# ArduFrauenfelderCNC_0_1-b8.net
KiCad netlist of a schematic drawn in EAGLE
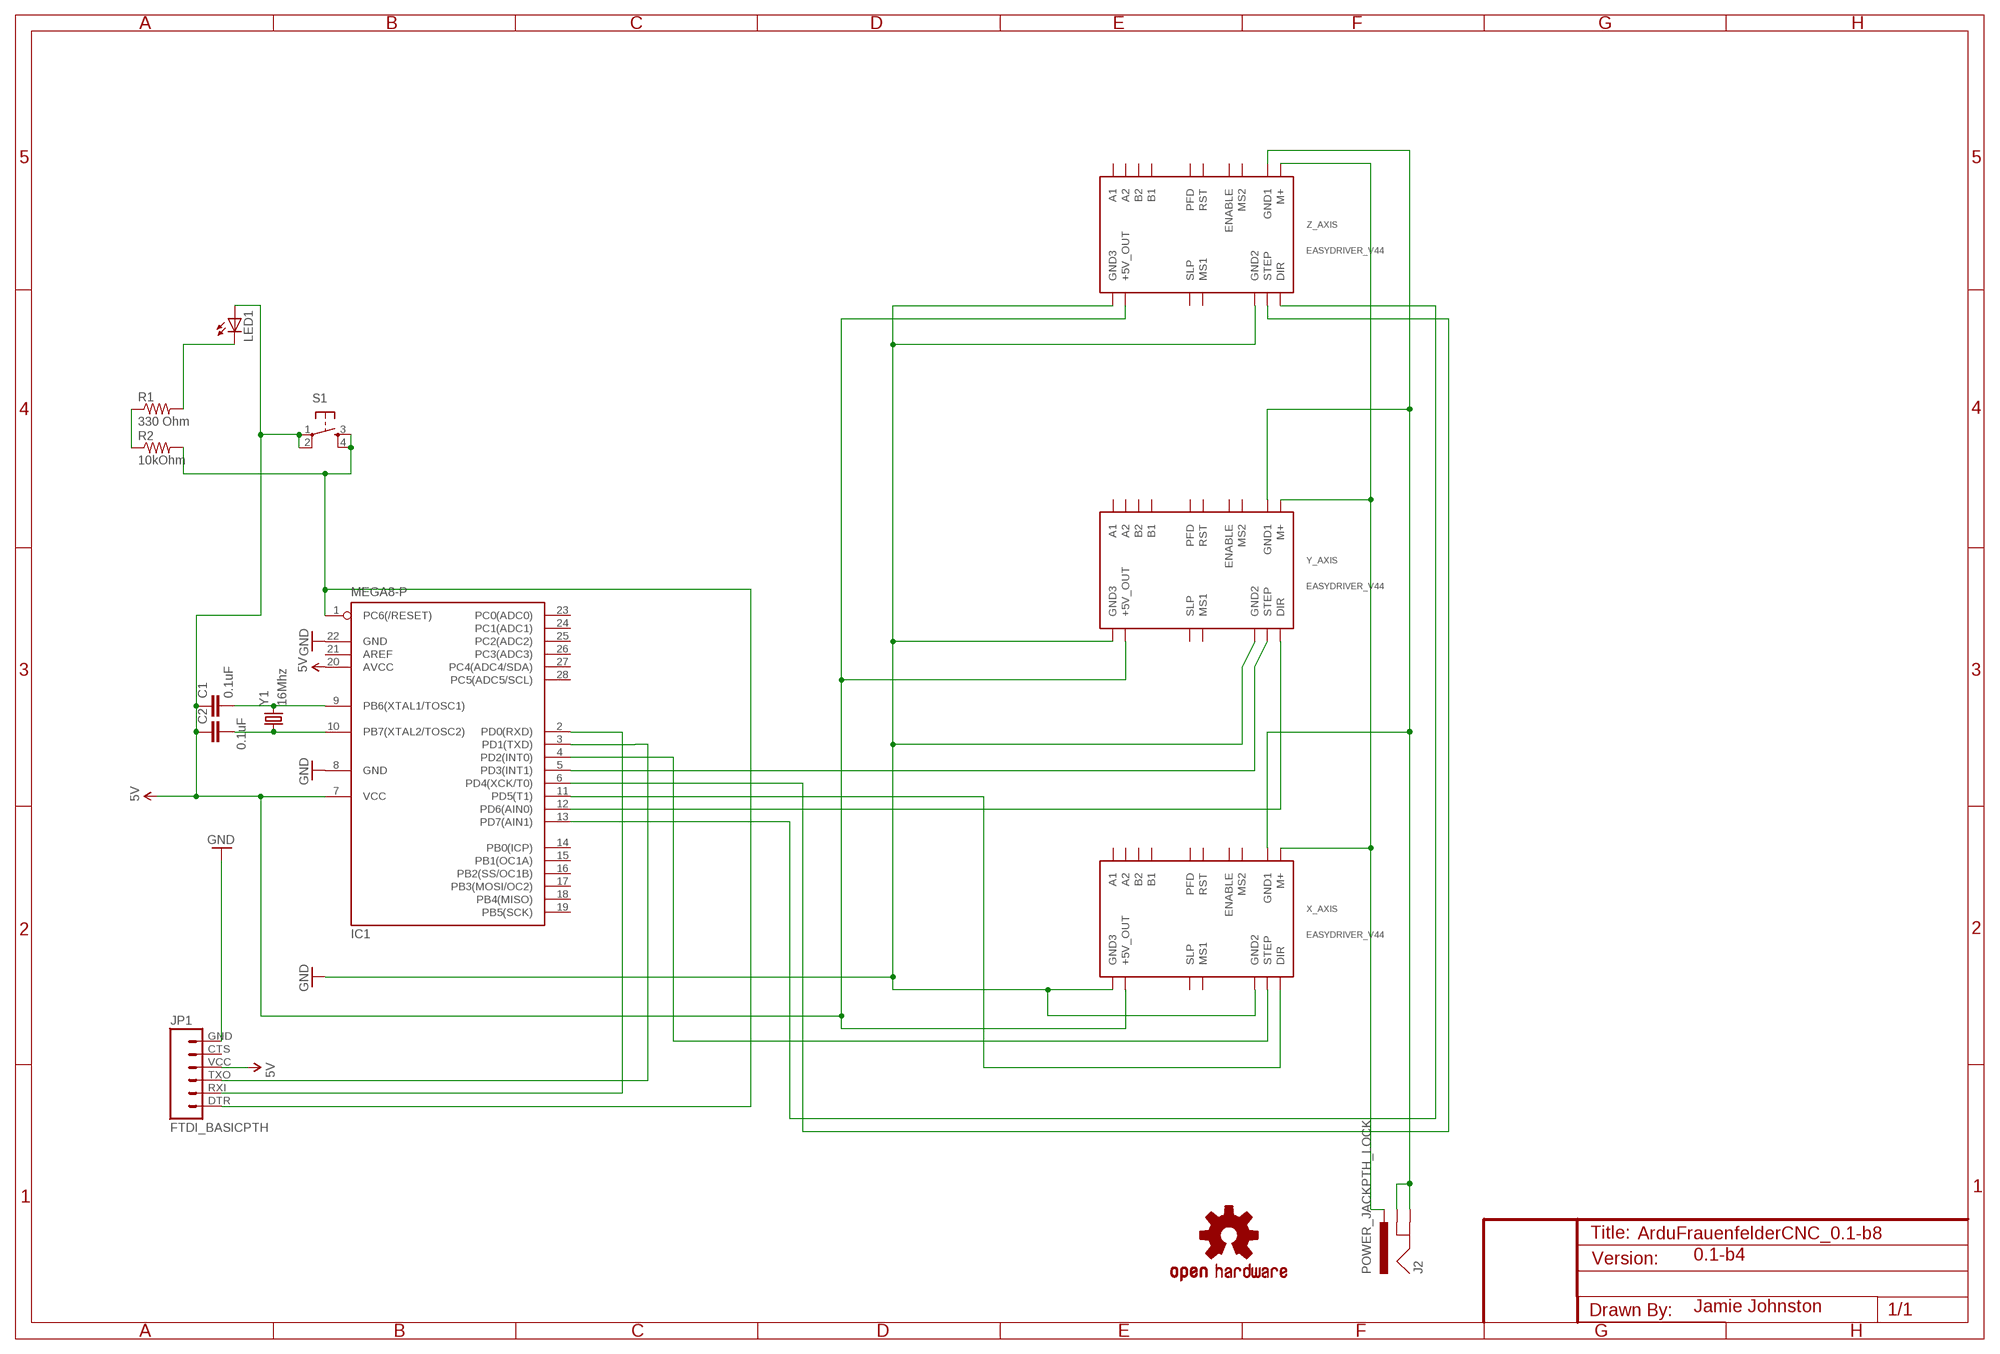
[diagram p0: schematic, sheet 1]

(export (version "E")
  (design (tool "Eeschema 10.0.6"))
  (components
    (comp (ref "C1")
      (value "0.1uF")
      (footprint "eagle-import:CAP-PTH-SMALL")
      (libsource (lib "eagle-import") (part "CAPPTH"))
    )
    (comp (ref "C2")
      (value "0.1uF")
      (footprint "eagle-import:CAP-PTH-SMALL")
      (libsource (lib "eagle-import") (part "CAPPTH"))
    )
    (comp (ref "IC1")
      (value "MEGA8-P")
      (footprint "eagle-import:DIL28-3")
      (libsource (lib "eagle-import") (part "MEGA8-P"))
    )
    (comp (ref "J2")
      (value "POWER_JACKPTH_LOCK")
      (footprint "eagle-import:POWER_JACK_PTH_LOCK")
      (libsource (lib "eagle-import") (part "POWER_JACKPTH_LOCK"))
    )
    (comp (ref "JP1")
      (value "FTDI_BASICPTH")
      (footprint "eagle-import:FTDI_BASIC")
      (libsource (lib "eagle-import") (part "FTDI_BASICPTH"))
    )
    (comp (ref "LED1")
      (value "LED5MM")
      (footprint "eagle-import:LED5MM")
      (libsource (lib "eagle-import") (part "LED5MM"))
    )
    (comp (ref "R1")
      (value "330 Ohm")
      (footprint "eagle-import:AXIAL-0.4")
      (libsource (lib "eagle-import") (part "RESISTORPTH-1/4W"))
    )
    (comp (ref "R2")
      (value "10kOhm")
      (footprint "eagle-import:AXIAL-0.4")
      (libsource (lib "eagle-import") (part "RESISTORPTH-1/4W"))
    )
    (comp (ref "S1")
      (value "TAC_SWITCHPTH")
      (footprint "eagle-import:TACTILE-PTH")
      (libsource (lib "eagle-import") (part "TAC_SWITCHPTH"))
    )
    (comp (ref "U$2")
      (value "OSHW-LOGOL")
      (footprint "eagle-import:OSHW-LOGO-L")
      (libsource (lib "eagle-import") (part "OSHW-LOGOL"))
    )
    (comp (ref "X_AXIS")
      (value "EASYDRIVER_V44")
      (footprint "eagle-import:EASYDRIVER_V44")
      (libsource (lib "eagle-import") (part "EASYDRIVER_V44"))
    )
    (comp (ref "Y1")
      (value "16Mhz")
      (footprint "eagle-import:HC49US")
      (libsource (lib "eagle-import") (part "CRYSTALHC49US"))
    )
    (comp (ref "Y_AXIS")
      (value "EASYDRIVER_V44")
      (footprint "eagle-import:EASYDRIVER_V44")
      (libsource (lib "eagle-import") (part "EASYDRIVER_V44"))
    )
    (comp (ref "Z_AXIS")
      (value "EASYDRIVER_V44")
      (footprint "eagle-import:EASYDRIVER_V44")
      (libsource (lib "eagle-import") (part "EASYDRIVER_V44"))
    )
  )
  (nets
    (net (code "1") (name "5V") (class "Default")
      (node (ref "C1") (pin "1") (pinfunction "1_1") (pintype "passive"))
      (node (ref "C2") (pin "1") (pinfunction "1_1") (pintype "passive"))
      (node (ref "IC1") (pin "20") (pinfunction "AVCC_20") (pintype "power_in"))
      (node (ref "IC1") (pin "7") (pinfunction "VCC_7") (pintype "power_in"))
      (node (ref "JP1") (pin "VCC") (pinfunction "4_VCC") (pintype "passive"))
      (node (ref "LED1") (pin "A") (pinfunction "A_A") (pintype "passive"))
      (node (ref "S1") (pin "1") (pinfunction "1_1") (pintype "passive"))
      (node (ref "S1") (pin "2") (pinfunction "2_2") (pintype "passive"))
      (node (ref "X_AXIS") (pin "P$11") (pinfunction "+5V_OUT_P$11") (pintype "bidirectional"))
      (node (ref "Y_AXIS") (pin "P$11") (pinfunction "+5V_OUT_P$11") (pintype "bidirectional"))
      (node (ref "Z_AXIS") (pin "P$11") (pinfunction "+5V_OUT_P$11") (pintype "bidirectional"))
    )
    (net (code "2") (name "GND") (class "Default")
      (node (ref "IC1") (pin "22") (pinfunction "GND_22") (pintype "power_in"))
      (node (ref "IC1") (pin "8") (pinfunction "GND_8") (pintype "power_in"))
      (node (ref "JP1") (pin "GND") (pinfunction "6_GND") (pintype "passive"))
      (node (ref "X_AXIS") (pin "GND2") (pinfunction "GND2_GND2") (pintype "bidirectional"))
      (node (ref "X_AXIS") (pin "GND3") (pinfunction "GND3_GND3") (pintype "bidirectional"))
      (node (ref "Y_AXIS") (pin "GND2") (pinfunction "GND2_GND2") (pintype "bidirectional"))
      (node (ref "Y_AXIS") (pin "GND3") (pinfunction "GND3_GND3") (pintype "bidirectional"))
      (node (ref "Z_AXIS") (pin "GND2") (pinfunction "GND2_GND2") (pintype "bidirectional"))
      (node (ref "Z_AXIS") (pin "GND3") (pinfunction "GND3_GND3") (pintype "bidirectional"))
    )
    (net (code "3") (name "Net-(IC1-PB6(XTAL1{slash}TOSC1))") (class "Default")
      (node (ref "C1") (pin "2") (pinfunction "2_2") (pintype "passive"))
      (node (ref "IC1") (pin "9") (pinfunction "PB6(XTAL1/TOSC1)_9") (pintype "bidirectional"))
      (node (ref "Y1") (pin "2") (pinfunction "2_2") (pintype "passive"))
    )
    (net (code "4") (name "Net-(IC1-PB7(XTAL2{slash}TOSC2))") (class "Default")
      (node (ref "C2") (pin "2") (pinfunction "2_2") (pintype "passive"))
      (node (ref "IC1") (pin "10") (pinfunction "PB7(XTAL2/TOSC2)_10") (pintype "bidirectional"))
      (node (ref "Y1") (pin "1") (pinfunction "1_1") (pintype "passive"))
    )
    (net (code "5") (name "Net-(IC1-PC6({slash}RESET))") (class "Default")
      (node (ref "IC1") (pin "1") (pinfunction "PC6(/RESET)_1") (pintype "bidirectional"))
      (node (ref "JP1") (pin "DTR") (pinfunction "1_DTR") (pintype "passive"))
      (node (ref "R2") (pin "P$2") (pinfunction "2_P$2") (pintype "passive"))
      (node (ref "S1") (pin "3") (pinfunction "3_3") (pintype "passive"))
      (node (ref "S1") (pin "4") (pinfunction "4_4") (pintype "passive"))
    )
    (net (code "6") (name "Net-(IC1-PD0(RXD))") (class "Default")
      (node (ref "IC1") (pin "2") (pinfunction "PD0(RXD)_2") (pintype "bidirectional"))
      (node (ref "JP1") (pin "RXI") (pinfunction "2_RXI") (pintype "passive"))
    )
    (net (code "7") (name "Net-(IC1-PD1(TXD))") (class "Default")
      (node (ref "IC1") (pin "3") (pinfunction "PD1(TXD)_3") (pintype "bidirectional"))
      (node (ref "JP1") (pin "TXO") (pinfunction "3_TXO") (pintype "passive"))
    )
    (net (code "8") (name "Net-(IC1-PD2(INT0))") (class "Default")
      (node (ref "IC1") (pin "4") (pinfunction "PD2(INT0)_4") (pintype "bidirectional"))
      (node (ref "X_AXIS") (pin "STEP") (pinfunction "STEP_STEP") (pintype "bidirectional"))
    )
    (net (code "9") (name "Net-(IC1-PD3(INT1))") (class "Default")
      (node (ref "IC1") (pin "5") (pinfunction "PD3(INT1)_5") (pintype "bidirectional"))
      (node (ref "Y_AXIS") (pin "STEP") (pinfunction "STEP_STEP") (pintype "bidirectional"))
    )
    (net (code "10") (name "Net-(IC1-PD4(XCK{slash}T0))") (class "Default")
      (node (ref "IC1") (pin "6") (pinfunction "PD4(XCK/T0)_6") (pintype "bidirectional"))
      (node (ref "Z_AXIS") (pin "STEP") (pinfunction "STEP_STEP") (pintype "bidirectional"))
    )
    (net (code "11") (name "Net-(IC1-PD5(T1))") (class "Default")
      (node (ref "IC1") (pin "11") (pinfunction "PD5(T1)_11") (pintype "bidirectional"))
      (node (ref "X_AXIS") (pin "DIR") (pinfunction "DIR_DIR") (pintype "bidirectional"))
    )
    (net (code "12") (name "Net-(IC1-PD6(AIN0))") (class "Default")
      (node (ref "IC1") (pin "12") (pinfunction "PD6(AIN0)_12") (pintype "bidirectional"))
      (node (ref "Y_AXIS") (pin "DIR") (pinfunction "DIR_DIR") (pintype "bidirectional"))
    )
    (net (code "13") (name "Net-(IC1-PD7(AIN1))") (class "Default")
      (node (ref "IC1") (pin "13") (pinfunction "PD7(AIN1)_13") (pintype "bidirectional"))
      (node (ref "Z_AXIS") (pin "DIR") (pinfunction "DIR_DIR") (pintype "bidirectional"))
    )
    (net (code "14") (name "Net-(J2-PadGND)") (class "Default")
      (node (ref "J2") (pin "GND") (pinfunction "GND_GND") (pintype "bidirectional"))
      (node (ref "J2") (pin "GNDBREAK") (pinfunction "GNDBREAK_GNDBREAK") (pintype "bidirectional"))
      (node (ref "X_AXIS") (pin "GND1") (pinfunction "GND1_GND1") (pintype "bidirectional"))
      (node (ref "Y_AXIS") (pin "GND1") (pinfunction "GND1_GND1") (pintype "bidirectional"))
      (node (ref "Z_AXIS") (pin "GND1") (pinfunction "GND1_GND1") (pintype "bidirectional"))
    )
    (net (code "15") (name "Net-(J2-PadPWR)") (class "Default")
      (node (ref "J2") (pin "PWR") (pinfunction "PWR_PWR") (pintype "bidirectional"))
      (node (ref "X_AXIS") (pin "M+") (pinfunction "M+_M+") (pintype "bidirectional"))
      (node (ref "Y_AXIS") (pin "M+") (pinfunction "M+_M+") (pintype "bidirectional"))
      (node (ref "Z_AXIS") (pin "M+") (pinfunction "M+_M+") (pintype "bidirectional"))
    )
    (net (code "16") (name "Net-(LED1-C)") (class "Default")
      (node (ref "LED1") (pin "K") (pinfunction "C_K") (pintype "passive"))
      (node (ref "R1") (pin "P$2") (pinfunction "2_P$2") (pintype "passive"))
    )
    (net (code "17") (name "Net-(R1-1)") (class "Default")
      (node (ref "R1") (pin "P$1") (pinfunction "1_P$1") (pintype "passive"))
      (node (ref "R2") (pin "P$1") (pinfunction "1_P$1") (pintype "passive"))
    )
    (net (code "18") (name "unconnected-(IC1-AREF-Pad21)") (class "Default")
      (node (ref "IC1") (pin "21") (pinfunction "AREF_21") (pintype "passive"))
    )
    (net (code "19") (name "unconnected-(IC1-PB0(ICP)-Pad14)") (class "Default")
      (node (ref "IC1") (pin "14") (pinfunction "PB0(ICP)_14") (pintype "bidirectional"))
    )
    (net (code "20") (name "unconnected-(IC1-PB1(OC1A)-Pad15)") (class "Default")
      (node (ref "IC1") (pin "15") (pinfunction "PB1(OC1A)_15") (pintype "bidirectional"))
    )
    (net (code "21") (name "unconnected-(IC1-PB2(SS{slash}OC1B)-Pad16)") (class "Default")
      (node (ref "IC1") (pin "16") (pinfunction "PB2(SS/OC1B)_16") (pintype "bidirectional"))
    )
    (net (code "22") (name "unconnected-(IC1-PB3(MOSI{slash}OC2)-Pad17)") (class "Default")
      (node (ref "IC1") (pin "17") (pinfunction "PB3(MOSI/OC2)_17") (pintype "bidirectional"))
    )
    (net (code "23") (name "unconnected-(IC1-PB4(MISO)-Pad18)") (class "Default")
      (node (ref "IC1") (pin "18") (pinfunction "PB4(MISO)_18") (pintype "bidirectional"))
    )
    (net (code "24") (name "unconnected-(IC1-PB5(SCK)-Pad19)") (class "Default")
      (node (ref "IC1") (pin "19") (pinfunction "PB5(SCK)_19") (pintype "bidirectional"))
    )
    (net (code "25") (name "unconnected-(IC1-PC0(ADC0)-Pad23)") (class "Default")
      (node (ref "IC1") (pin "23") (pinfunction "PC0(ADC0)_23") (pintype "bidirectional"))
    )
    (net (code "26") (name "unconnected-(IC1-PC1(ADC1)-Pad24)") (class "Default")
      (node (ref "IC1") (pin "24") (pinfunction "PC1(ADC1)_24") (pintype "bidirectional"))
    )
    (net (code "27") (name "unconnected-(IC1-PC2(ADC2)-Pad25)") (class "Default")
      (node (ref "IC1") (pin "25") (pinfunction "PC2(ADC2)_25") (pintype "bidirectional"))
    )
    (net (code "28") (name "unconnected-(IC1-PC3(ADC3)-Pad26)") (class "Default")
      (node (ref "IC1") (pin "26") (pinfunction "PC3(ADC3)_26") (pintype "bidirectional"))
    )
    (net (code "29") (name "unconnected-(IC1-PC4(ADC4{slash}SDA)-Pad27)") (class "Default")
      (node (ref "IC1") (pin "27") (pinfunction "PC4(ADC4/SDA)_27") (pintype "bidirectional"))
    )
    (net (code "30") (name "unconnected-(IC1-PC5(ADC5{slash}SCL)-Pad28)") (class "Default")
      (node (ref "IC1") (pin "28") (pinfunction "PC5(ADC5/SCL)_28") (pintype "bidirectional"))
    )
    (net (code "31") (name "unconnected-(JP1-5-PadCTS)") (class "Default")
      (node (ref "JP1") (pin "CTS") (pinfunction "5_CTS") (pintype "passive"))
    )
    (net (code "32") (name "unconnected-(X_AXIS-PadA1)") (class "Default")
      (node (ref "X_AXIS") (pin "A1") (pinfunction "A1_A1") (pintype "bidirectional"))
    )
    (net (code "33") (name "unconnected-(X_AXIS-PadA2)") (class "Default")
      (node (ref "X_AXIS") (pin "A2") (pinfunction "A2_A2") (pintype "bidirectional"))
    )
    (net (code "34") (name "unconnected-(X_AXIS-PadB1)") (class "Default")
      (node (ref "X_AXIS") (pin "B1") (pinfunction "B1_B1") (pintype "bidirectional"))
    )
    (net (code "35") (name "unconnected-(X_AXIS-PadB2)") (class "Default")
      (node (ref "X_AXIS") (pin "B2") (pinfunction "B2_B2") (pintype "bidirectional"))
    )
    (net (code "36") (name "unconnected-(X_AXIS-PadENABLE)") (class "Default")
      (node (ref "X_AXIS") (pin "ENABLE") (pinfunction "ENABLE_ENABLE") (pintype "bidirectional"))
    )
    (net (code "37") (name "unconnected-(X_AXIS-PadMS1)") (class "Default")
      (node (ref "X_AXIS") (pin "MS1") (pinfunction "MS1_MS1") (pintype "bidirectional"))
    )
    (net (code "38") (name "unconnected-(X_AXIS-PadMS2)") (class "Default")
      (node (ref "X_AXIS") (pin "MS2") (pinfunction "MS2_MS2") (pintype "bidirectional"))
    )
    (net (code "39") (name "unconnected-(X_AXIS-PadPFD)") (class "Default")
      (node (ref "X_AXIS") (pin "PFD") (pinfunction "PFD_PFD") (pintype "bidirectional"))
    )
    (net (code "40") (name "unconnected-(X_AXIS-PadRST)") (class "Default")
      (node (ref "X_AXIS") (pin "RST") (pinfunction "RST_RST") (pintype "bidirectional"))
    )
    (net (code "41") (name "unconnected-(X_AXIS-SLP-PadSLEEP)") (class "Default")
      (node (ref "X_AXIS") (pin "SLEEP") (pinfunction "SLP_SLEEP") (pintype "bidirectional"))
    )
    (net (code "42") (name "unconnected-(Y_AXIS-PadA1)") (class "Default")
      (node (ref "Y_AXIS") (pin "A1") (pinfunction "A1_A1") (pintype "bidirectional"))
    )
    (net (code "43") (name "unconnected-(Y_AXIS-PadA2)") (class "Default")
      (node (ref "Y_AXIS") (pin "A2") (pinfunction "A2_A2") (pintype "bidirectional"))
    )
    (net (code "44") (name "unconnected-(Y_AXIS-PadB1)") (class "Default")
      (node (ref "Y_AXIS") (pin "B1") (pinfunction "B1_B1") (pintype "bidirectional"))
    )
    (net (code "45") (name "unconnected-(Y_AXIS-PadB2)") (class "Default")
      (node (ref "Y_AXIS") (pin "B2") (pinfunction "B2_B2") (pintype "bidirectional"))
    )
    (net (code "46") (name "unconnected-(Y_AXIS-PadENABLE)") (class "Default")
      (node (ref "Y_AXIS") (pin "ENABLE") (pinfunction "ENABLE_ENABLE") (pintype "bidirectional"))
    )
    (net (code "47") (name "unconnected-(Y_AXIS-PadMS1)") (class "Default")
      (node (ref "Y_AXIS") (pin "MS1") (pinfunction "MS1_MS1") (pintype "bidirectional"))
    )
    (net (code "48") (name "unconnected-(Y_AXIS-PadMS2)") (class "Default")
      (node (ref "Y_AXIS") (pin "MS2") (pinfunction "MS2_MS2") (pintype "bidirectional"))
    )
    (net (code "49") (name "unconnected-(Y_AXIS-PadPFD)") (class "Default")
      (node (ref "Y_AXIS") (pin "PFD") (pinfunction "PFD_PFD") (pintype "bidirectional"))
    )
    (net (code "50") (name "unconnected-(Y_AXIS-PadRST)") (class "Default")
      (node (ref "Y_AXIS") (pin "RST") (pinfunction "RST_RST") (pintype "bidirectional"))
    )
    (net (code "51") (name "unconnected-(Y_AXIS-SLP-PadSLEEP)") (class "Default")
      (node (ref "Y_AXIS") (pin "SLEEP") (pinfunction "SLP_SLEEP") (pintype "bidirectional"))
    )
    (net (code "52") (name "unconnected-(Z_AXIS-PadA1)") (class "Default")
      (node (ref "Z_AXIS") (pin "A1") (pinfunction "A1_A1") (pintype "bidirectional"))
    )
    (net (code "53") (name "unconnected-(Z_AXIS-PadA2)") (class "Default")
      (node (ref "Z_AXIS") (pin "A2") (pinfunction "A2_A2") (pintype "bidirectional"))
    )
    (net (code "54") (name "unconnected-(Z_AXIS-PadB1)") (class "Default")
      (node (ref "Z_AXIS") (pin "B1") (pinfunction "B1_B1") (pintype "bidirectional"))
    )
    (net (code "55") (name "unconnected-(Z_AXIS-PadB2)") (class "Default")
      (node (ref "Z_AXIS") (pin "B2") (pinfunction "B2_B2") (pintype "bidirectional"))
    )
    (net (code "56") (name "unconnected-(Z_AXIS-PadENABLE)") (class "Default")
      (node (ref "Z_AXIS") (pin "ENABLE") (pinfunction "ENABLE_ENABLE") (pintype "bidirectional"))
    )
    (net (code "57") (name "unconnected-(Z_AXIS-PadMS1)") (class "Default")
      (node (ref "Z_AXIS") (pin "MS1") (pinfunction "MS1_MS1") (pintype "bidirectional"))
    )
    (net (code "58") (name "unconnected-(Z_AXIS-PadMS2)") (class "Default")
      (node (ref "Z_AXIS") (pin "MS2") (pinfunction "MS2_MS2") (pintype "bidirectional"))
    )
    (net (code "59") (name "unconnected-(Z_AXIS-PadPFD)") (class "Default")
      (node (ref "Z_AXIS") (pin "PFD") (pinfunction "PFD_PFD") (pintype "bidirectional"))
    )
    (net (code "60") (name "unconnected-(Z_AXIS-PadRST)") (class "Default")
      (node (ref "Z_AXIS") (pin "RST") (pinfunction "RST_RST") (pintype "bidirectional"))
    )
    (net (code "61") (name "unconnected-(Z_AXIS-SLP-PadSLEEP)") (class "Default")
      (node (ref "Z_AXIS") (pin "SLEEP") (pinfunction "SLP_SLEEP") (pintype "bidirectional"))
    )
  )
)
